# AD8253.net
KiCad netlist of a schematic drawn in Altium Designer
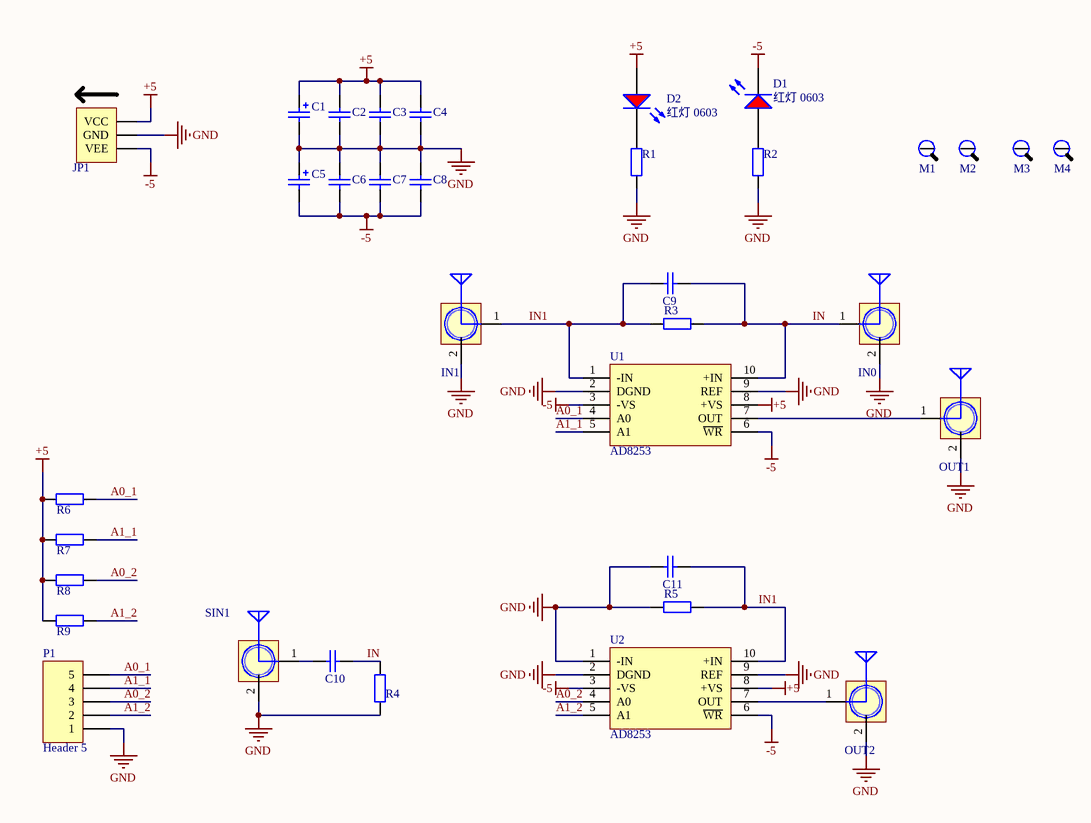
[diagram p0: AD8253.SchDoc]

(export (version "E")
  (design (tool "Eeschema 10.0.6"))
  (components
    (comp (ref "C1")
      (value "10uF (106) ±10% 16V")
      (footprint "CASE-A_3216")
      (description "钽电容")
      (libsource (lib "JLC") (part "3216 10uF (106) 10% 16V"))
    )
    (comp (ref "C2")
      (value "100nF (104) 10% 50V")
      (footprint "0603_C")
      (description "贴片电容")
      (libsource (lib "JLC") (part "0603 100nF (104) 10% 50V"))
    )
    (comp (ref "C3")
      (value "100nF (104) 10% 50V")
      (footprint "0603_C")
      (description "贴片电容")
      (libsource (lib "JLC") (part "0603 100nF (104) 10% 50V"))
    )
    (comp (ref "C4")
      (value "100nF (104) 10% 50V")
      (footprint "0603_C")
      (description "贴片电容")
      (libsource (lib "JLC") (part "0603 100nF (104) 10% 50V"))
    )
    (comp (ref "C5")
      (value "10uF (106) ±10% 16V")
      (footprint "CASE-A_3216")
      (description "钽电容")
      (libsource (lib "JLC") (part "3216 10uF (106) 10% 16V"))
    )
    (comp (ref "C6")
      (value "100nF (104) 10% 50V")
      (footprint "0603_C")
      (description "贴片电容")
      (libsource (lib "JLC") (part "0603 100nF (104) 10% 50V"))
    )
    (comp (ref "C7")
      (value "100nF (104) 10% 50V")
      (footprint "0603_C")
      (description "贴片电容")
      (libsource (lib "JLC") (part "0603 100nF (104) 10% 50V"))
    )
    (comp (ref "C8")
      (value "100nF (104) 10% 50V")
      (footprint "0603_C")
      (description "贴片电容")
      (libsource (lib "JLC") (part "0603 100nF (104) 10% 50V"))
    )
    (comp (ref "C9")
      (value "1.5nF (152) 10% 50V")
      (footprint "0603_C")
      (description "贴片电容")
      (libsource (lib "JLC") (part "0603 1.5nF (152) 10% 50V"))
    )
    (comp (ref "C10")
      (value "1.5nF (152) 10% 50V")
      (footprint "0603_C")
      (description "贴片电容")
      (libsource (lib "JLC") (part "0603 1.5nF (152) 10% 50V"))
    )
    (comp (ref "C11")
      (value "1.5nF (152) 10% 50V")
      (footprint "0603_C")
      (description "贴片电容")
      (libsource (lib "JLC") (part "0603 1.5nF (152) 10% 50V"))
    )
    (comp (ref "D1")
      (value "红灯 0603")
      (footprint "0603_LED_S1")
      (description "发光二极管")
      (libsource (lib "JLC") (part "0603 红灯"))
    )
    (comp (ref "D2")
      (value "红灯 0603")
      (footprint "0603_LED_S1")
      (description "发光二极管")
      (libsource (lib "JLC") (part "0603 红灯"))
    )
    (comp (ref "IN0")
      (value "SMA WIFI 天线接口")
      (footprint "SMA")
      (description "SMA-2.4G射频天线接口")
      (fields (field (name "版权归属") "源创客"))
      (libsource (lib "Cooperation") (part "PORT_SMA"))
    )
    (comp (ref "IN1")
      (value "SMA WIFI 天线接口")
      (footprint "SMA")
      (description "SMA-2.4G射频天线接口")
      (fields (field (name "版权归属") "源创客"))
      (libsource (lib "") (part "PORT_SMA_1"))
    )
    (comp (ref "JP1")
      (value "HDR-1X3")
      (footprint "Power_IN_3.81-3P")
      (description "3P接插件,模块双电源供电口")
      (fields (field (name "版权归属") "源创客"))
      (libsource (lib "Cooperation") (part "PORT_Power_IN3"))
    )
    (comp (ref "M1")
      (value "M3")
      (footprint "M3x10_L")
      (description "螺丝")
      (libsource (lib "Cooperation") (part "ELSE_M3_screw"))
    )
    (comp (ref "M2")
      (value "M3")
      (footprint "M3x10_L")
      (description "螺丝")
      (libsource (lib "Cooperation") (part "ELSE_M3_screw"))
    )
    (comp (ref "M3")
      (value "M3")
      (footprint "M3x10_L")
      (description "螺丝")
      (libsource (lib "Cooperation") (part "ELSE_M3_screw"))
    )
    (comp (ref "M4")
      (value "M3")
      (footprint "M3x10_L")
      (description "螺丝")
      (libsource (lib "Cooperation") (part "ELSE_M3_screw"))
    )
    (comp (ref "OUT1")
      (value "SMA WIFI 天线接口")
      (footprint "SMA")
      (description "SMA-2.4G射频天线接口")
      (fields (field (name "版权归属") "源创客"))
      (libsource (lib "Cooperation") (part "PORT_SMA"))
    )
    (comp (ref "OUT2")
      (value "SMA WIFI 天线接口")
      (footprint "SMA")
      (description "SMA-2.4G射频天线接口")
      (fields (field (name "版权归属") "源创客"))
      (libsource (lib "Cooperation") (part "PORT_SMA"))
    )
    (comp (ref "P1")
      (value "Header 5")
      (footprint "HDR1X5")
      (description "Header, 5-Pin")
      (fields (field (name "PUBLISHER") "Altium Limited"))
      (libsource (lib "Miscellaneous Connectors") (part "Header 5"))
    )
    (comp (ref "R1")
      (value "10KΩ (1002) ±1%")
      (footprint "0603_R")
      (description "贴片电阻")
      (libsource (lib "JLC") (part "0603 10KΩ (1002) 1%"))
    )
    (comp (ref "R2")
      (value "10KΩ (1002) ±1%")
      (footprint "0603_R")
      (description "贴片电阻")
      (libsource (lib "JLC") (part "0603 10KΩ (1002) 1%"))
    )
    (comp (ref "R3")
      (value "110Ω (1100) ±1%")
      (footprint "0603_R")
      (description "贴片电阻")
      (libsource (lib "") (part "0603 110Ω (1100) 1%_2"))
    )
    (comp (ref "R4")
      (value "110Ω (1100) ±1%")
      (footprint "0603_R")
      (description "贴片电阻")
      (libsource (lib "") (part "0603 110Ω (1100) 1%_1"))
    )
    (comp (ref "R5")
      (value "110Ω (1100) ±1%")
      (footprint "0603_R")
      (description "贴片电阻")
      (libsource (lib "") (part "0603 110Ω (1100) 1%_2"))
    )
    (comp (ref "R6")
      (value "110Ω (1100) ±1%")
      (footprint "0603_R")
      (description "贴片电阻")
      (libsource (lib "JLC") (part "0603 110Ω (1100) 1%"))
    )
    (comp (ref "R7")
      (value "110Ω (1100) ±1%")
      (footprint "0603_R")
      (description "贴片电阻")
      (libsource (lib "JLC") (part "0603 110Ω (1100) 1%"))
    )
    (comp (ref "R8")
      (value "110Ω (1100) ±1%")
      (footprint "0603_R")
      (description "贴片电阻")
      (libsource (lib "JLC") (part "0603 110Ω (1100) 1%"))
    )
    (comp (ref "R9")
      (value "110Ω (1100) ±1%")
      (footprint "0603_R")
      (description "贴片电阻")
      (libsource (lib "JLC") (part "0603 110Ω (1100) 1%"))
    )
    (comp (ref "SIN1")
      (value "SMA WIFI 天线接口")
      (footprint "SMA")
      (description "SMA-2.4G射频天线接口")
      (fields (field (name "版权归属") "源创客"))
      (libsource (lib "") (part "PORT_SMA_1"))
    )
    (comp (ref "U1") (value "AD8253") (footprint "MSOP10_M") (libsource (lib "Cooperation") (part "AD8253")))
    (comp (ref "U2") (value "AD8253") (footprint "MSOP10_M") (libsource (lib "Cooperation") (part "AD8253")))
  )
  (nets
    (net (code "1") (name "+5") (class "Default")
      (node (ref "C1") (pin "1") (pinfunction "1_1") (pintype "passive"))
      (node (ref "C2") (pin "2") (pinfunction "2_2") (pintype "passive"))
      (node (ref "C3") (pin "2") (pinfunction "2_2") (pintype "passive"))
      (node (ref "C4") (pin "2") (pinfunction "2_2") (pintype "passive"))
      (node (ref "D2") (pin "A") (pinfunction "A_A") (pintype "passive"))
      (node (ref "JP1") (pin "1") (pinfunction "VCC_1") (pintype "passive"))
      (node (ref "R6") (pin "2") (pinfunction "2_2") (pintype "passive"))
      (node (ref "R7") (pin "2") (pinfunction "2_2") (pintype "passive"))
      (node (ref "R8") (pin "2") (pinfunction "2_2") (pintype "passive"))
      (node (ref "R9") (pin "2") (pinfunction "2_2") (pintype "passive"))
      (node (ref "U1") (pin "8") (pinfunction "+VS_8") (pintype "passive"))
      (node (ref "U2") (pin "8") (pinfunction "+VS_8") (pintype "passive"))
    )
    (net (code "2") (name "-5") (class "Default")
      (node (ref "C5") (pin "2") (pinfunction "2_2") (pintype "passive"))
      (node (ref "C6") (pin "1") (pinfunction "1_1") (pintype "passive"))
      (node (ref "C7") (pin "1") (pinfunction "1_1") (pintype "passive"))
      (node (ref "C8") (pin "1") (pinfunction "1_1") (pintype "passive"))
      (node (ref "D1") (pin "K") (pinfunction "K_K") (pintype "passive"))
      (node (ref "JP1") (pin "3") (pinfunction "VEE_3") (pintype "passive"))
      (node (ref "U1") (pin "3") (pinfunction "-VS_3") (pintype "passive"))
      (node (ref "U1") (pin "6") (pinfunction "~{WR}_6") (pintype "passive"))
      (node (ref "U2") (pin "3") (pinfunction "-VS_3") (pintype "passive"))
      (node (ref "U2") (pin "6") (pinfunction "~{WR}_6") (pintype "passive"))
    )
    (net (code "3") (name "/A0_1") (class "Default")
      (node (ref "P1") (pin "5") (pinfunction "5_5") (pintype "passive"))
      (node (ref "R6") (pin "1") (pinfunction "1_1") (pintype "passive"))
      (node (ref "U1") (pin "4") (pinfunction "A0_4") (pintype "passive"))
    )
    (net (code "4") (name "/A0_2") (class "Default")
      (node (ref "P1") (pin "3") (pinfunction "3_3") (pintype "passive"))
      (node (ref "R8") (pin "1") (pinfunction "1_1") (pintype "passive"))
      (node (ref "U2") (pin "4") (pinfunction "A0_4") (pintype "passive"))
    )
    (net (code "5") (name "/A1_1") (class "Default")
      (node (ref "P1") (pin "4") (pinfunction "4_4") (pintype "passive"))
      (node (ref "R7") (pin "1") (pinfunction "1_1") (pintype "passive"))
      (node (ref "U1") (pin "5") (pinfunction "A1_5") (pintype "passive"))
    )
    (net (code "6") (name "/A1_2") (class "Default")
      (node (ref "P1") (pin "2") (pinfunction "2_2") (pintype "passive"))
      (node (ref "R9") (pin "1") (pinfunction "1_1") (pintype "passive"))
      (node (ref "U2") (pin "5") (pinfunction "A1_5") (pintype "passive"))
    )
    (net (code "7") (name "/IN") (class "Default")
      (node (ref "C10") (pin "1") (pinfunction "1_1") (pintype "passive"))
      (node (ref "C9") (pin "1") (pinfunction "1_1") (pintype "passive"))
      (node (ref "IN0") (pin "1") (pinfunction "SINGLE_1") (pintype "passive"))
      (node (ref "R3") (pin "2") (pinfunction "2_2") (pintype "passive"))
      (node (ref "R4") (pin "2") (pinfunction "2_2") (pintype "passive"))
      (node (ref "U1") (pin "10") (pinfunction "+IN_10") (pintype "passive"))
    )
    (net (code "8") (name "/IN1") (class "Default")
      (node (ref "C11") (pin "1") (pinfunction "1_1") (pintype "passive"))
      (node (ref "C9") (pin "2") (pinfunction "2_2") (pintype "passive"))
      (node (ref "IN1") (pin "1") (pinfunction "SINGLE_1") (pintype "passive"))
      (node (ref "R3") (pin "1") (pinfunction "1_1") (pintype "passive"))
      (node (ref "R5") (pin "2") (pinfunction "2_2") (pintype "passive"))
      (node (ref "U1") (pin "1") (pinfunction "-IN_1") (pintype "passive"))
      (node (ref "U2") (pin "10") (pinfunction "+IN_10") (pintype "passive"))
    )
    (net (code "9") (name "GND") (class "Default")
      (node (ref "C1") (pin "2") (pinfunction "2_2") (pintype "passive"))
      (node (ref "C11") (pin "2") (pinfunction "2_2") (pintype "passive"))
      (node (ref "C2") (pin "1") (pinfunction "1_1") (pintype "passive"))
      (node (ref "C3") (pin "1") (pinfunction "1_1") (pintype "passive"))
      (node (ref "C4") (pin "1") (pinfunction "1_1") (pintype "passive"))
      (node (ref "C5") (pin "1") (pinfunction "1_1") (pintype "passive"))
      (node (ref "C6") (pin "2") (pinfunction "2_2") (pintype "passive"))
      (node (ref "C7") (pin "2") (pinfunction "2_2") (pintype "passive"))
      (node (ref "C8") (pin "2") (pinfunction "2_2") (pintype "passive"))
      (node (ref "IN0") (pin "2") (pinfunction "2_2") (pintype "passive"))
      (node (ref "IN1") (pin "2") (pinfunction "2_2") (pintype "passive"))
      (node (ref "JP1") (pin "2") (pinfunction "GND_2") (pintype "passive"))
      (node (ref "OUT1") (pin "2") (pinfunction "2_2") (pintype "passive"))
      (node (ref "OUT2") (pin "2") (pinfunction "2_2") (pintype "passive"))
      (node (ref "P1") (pin "1") (pinfunction "1_1") (pintype "passive"))
      (node (ref "R1") (pin "1") (pinfunction "1_1") (pintype "passive"))
      (node (ref "R2") (pin "1") (pinfunction "1_1") (pintype "passive"))
      (node (ref "R4") (pin "1") (pinfunction "1_1") (pintype "passive"))
      (node (ref "R5") (pin "1") (pinfunction "1_1") (pintype "passive"))
      (node (ref "SIN1") (pin "2") (pinfunction "2_2") (pintype "passive"))
      (node (ref "U1") (pin "2") (pinfunction "DGND_2") (pintype "passive"))
      (node (ref "U1") (pin "9") (pinfunction "REF_9") (pintype "passive"))
      (node (ref "U2") (pin "1") (pinfunction "-IN_1") (pintype "passive"))
      (node (ref "U2") (pin "2") (pinfunction "DGND_2") (pintype "passive"))
      (node (ref "U2") (pin "9") (pinfunction "REF_9") (pintype "passive"))
    )
    (net (code "10") (name "Net-(D1-PadA)") (class "Default")
      (node (ref "D1") (pin "A") (pinfunction "A_A") (pintype "passive"))
      (node (ref "R2") (pin "2") (pinfunction "2_2") (pintype "passive"))
    )
    (net (code "11") (name "Net-(D2-PadK)") (class "Default")
      (node (ref "D2") (pin "K") (pinfunction "K_K") (pintype "passive"))
      (node (ref "R1") (pin "2") (pinfunction "2_2") (pintype "passive"))
    )
    (net (code "12") (name "Net-(OUT1-SINGLE)") (class "Default")
      (node (ref "OUT1") (pin "1") (pinfunction "SINGLE_1") (pintype "passive"))
      (node (ref "U1") (pin "7") (pinfunction "OUT_7") (pintype "passive"))
    )
    (net (code "13") (name "Net-(OUT2-SINGLE)") (class "Default")
      (node (ref "OUT2") (pin "1") (pinfunction "SINGLE_1") (pintype "passive"))
      (node (ref "U2") (pin "7") (pinfunction "OUT_7") (pintype "passive"))
    )
    (net (code "14") (name "Net-(SIN1-SINGLE)") (class "Default")
      (node (ref "C10") (pin "2") (pinfunction "2_2") (pintype "passive"))
      (node (ref "SIN1") (pin "1") (pinfunction "SINGLE_1") (pintype "passive"))
    )
    (net (code "15") (name "unconnected-(M1-Pad1)") (class "Default")
      (node (ref "M1") (pin "1") (pinfunction "1_1") (pintype "passive"))
    )
    (net (code "16") (name "unconnected-(M2-Pad1)") (class "Default")
      (node (ref "M2") (pin "1") (pinfunction "1_1") (pintype "passive"))
    )
    (net (code "17") (name "unconnected-(M3-Pad1)") (class "Default")
      (node (ref "M3") (pin "1") (pinfunction "1_1") (pintype "passive"))
    )
    (net (code "18") (name "unconnected-(M4-Pad1)") (class "Default")
      (node (ref "M4") (pin "1") (pinfunction "1_1") (pintype "passive"))
    )
  )
)
